# rw-linear-17mm-mk-1_0.net
KiCad netlist of a schematic drawn in EAGLE
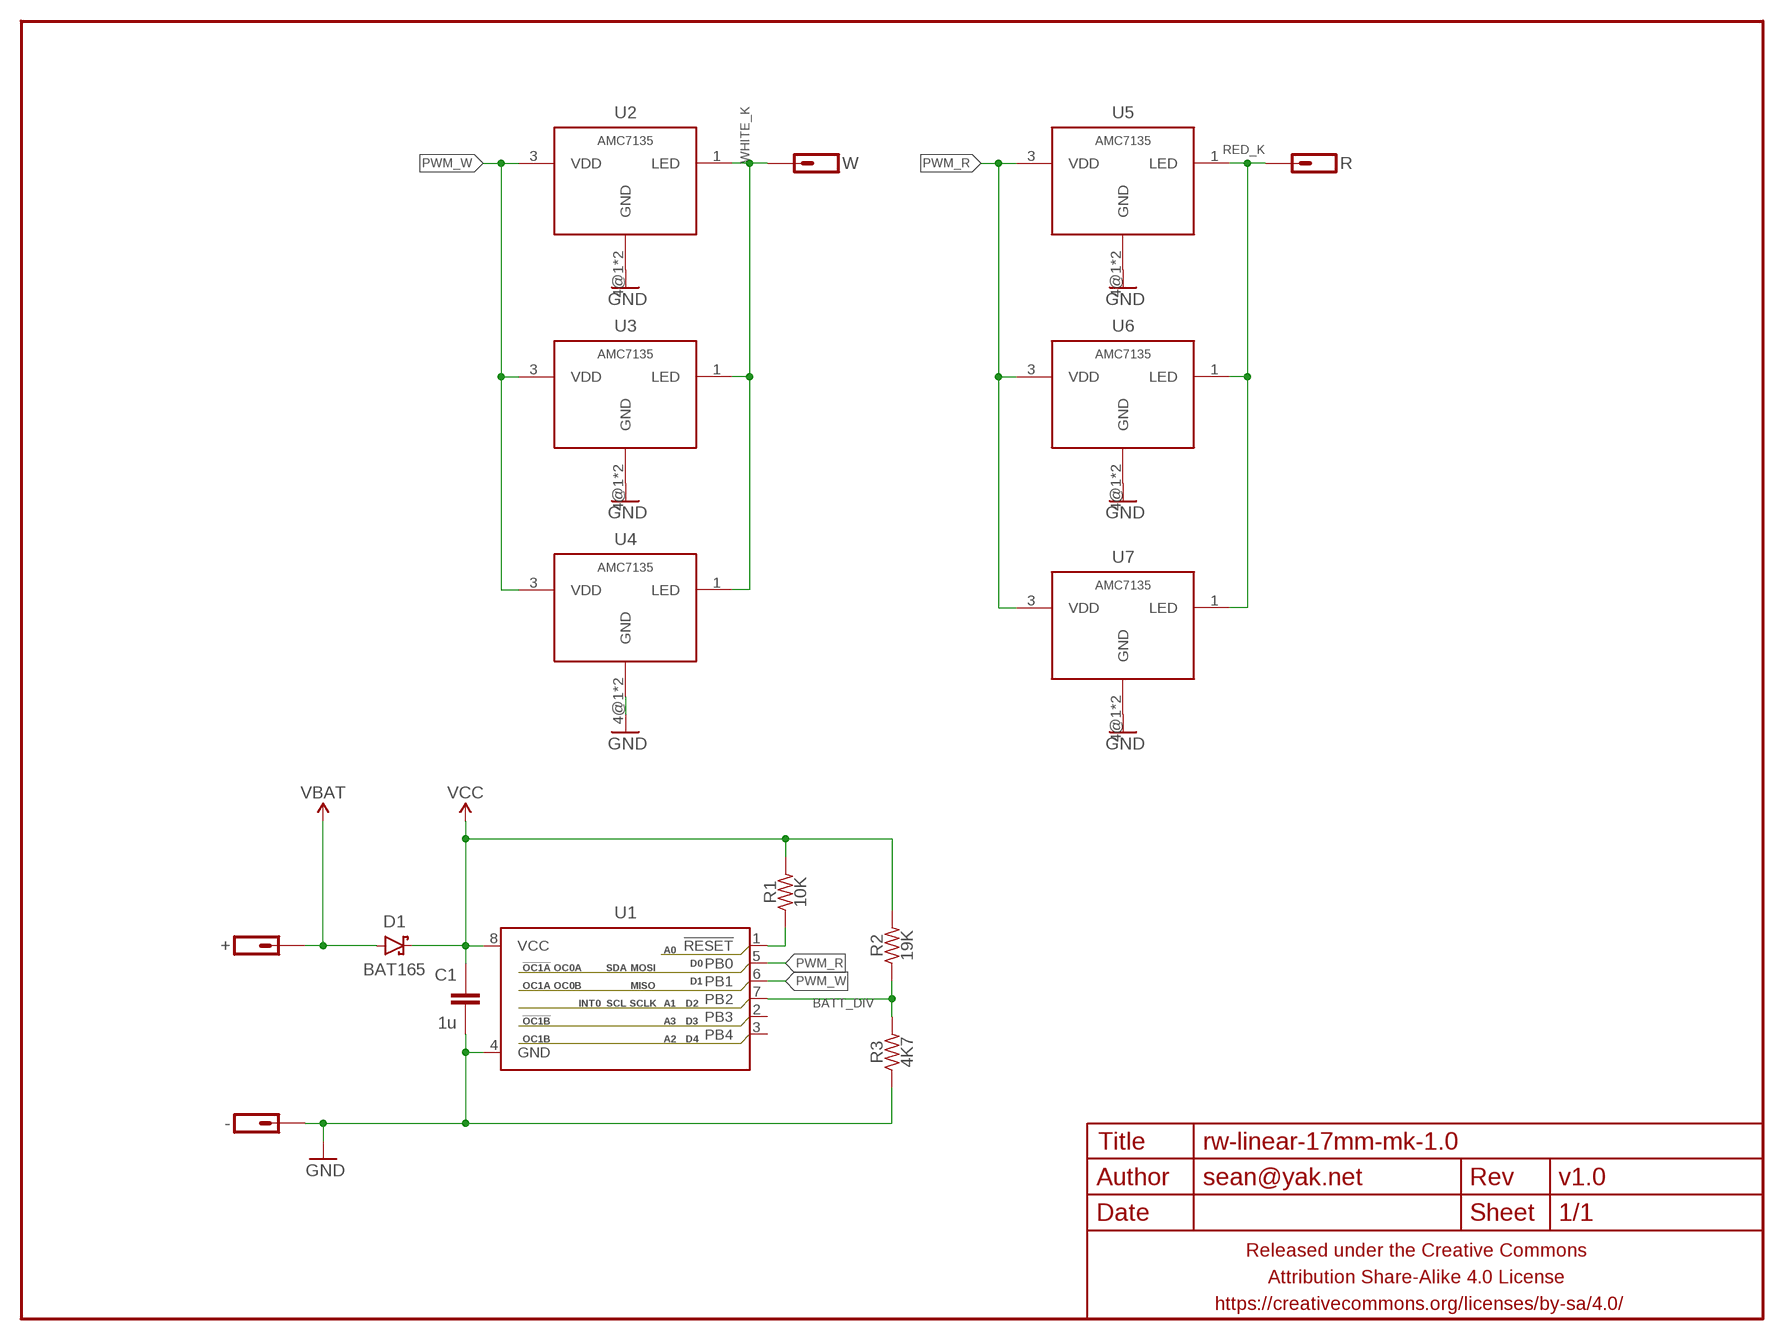
[diagram p0: schematic, sheet 1]

(export (version "E")
  (design (tool "Eeschema 10.0.6"))
  (components
    (comp (ref "+")
      (value "M01PTH-1.2MM-NS")
      (footprint "eagle-import:1X01-1.2MM-NS")
      (libsource (lib "eagle-import") (part "M01PTH-1.2MM-NS"))
    )
    (comp (ref "-")
      (value "M01NOT-A-VIA-NOPE")
      (footprint "eagle-import:1X01_NOSILK_NOSTOP")
      (libsource (lib "eagle-import") (part "M01NOT-A-VIA-NOPE"))
    )
    (comp (ref "C1")
      (value "1u")
      (footprint "eagle-import:C0402")
      (libsource (lib "eagle-import") (part "CAPACITOR-CERAMICC0402"))
    )
    (comp (ref "D1")
      (value "BAT165")
      (footprint "eagle-import:SOD323-SCHOTTKY")
      (libsource (lib "eagle-import") (part "DIODE-SCHOTTKYSOD323"))
    )
    (comp (ref "FRAME1")
      (value "FRAME-LETTERNO_PACKAGE")
      (footprint "eagle-import:DUMMY")
      (fields (field (name "DESIGNER") "sean@yak.net") (field (name "VERSION") "v1.0"))
      (libsource (lib "eagle-import") (part "FRAME-LETTERNO_PACKAGE"))
    )
    (comp (ref "R")
      (value "M01SMD-1.25MM-DIA")
      (footprint "eagle-import:1X01-SMD-1.25MM-DIA-NS")
      (libsource (lib "eagle-import") (part "M01SMD-1.25MM-DIA"))
    )
    (comp (ref "R1")
      (value "10K")
      (footprint "eagle-import:R0402")
      (libsource (lib "eagle-import") (part "RESISTORR0402"))
    )
    (comp (ref "R2")
      (value "19K")
      (footprint "eagle-import:R0402")
      (libsource (lib "eagle-import") (part "RESISTORR0402"))
    )
    (comp (ref "R3")
      (value "4K7")
      (footprint "eagle-import:R0402")
      (libsource (lib "eagle-import") (part "RESISTORR0402"))
    )
    (comp (ref "U1")
      (value "ATTINY13SOIC-NARROWPADS")
      (footprint "eagle-import:SO08-NARROWER")
      (libsource (lib "eagle-import") (part "ATTINY13SOIC-NARROWPADS"))
    )
    (comp (ref "U2")
      (value "AMC7135")
      (footprint "eagle-import:SOT89-NOTHERM")
      (libsource (lib "eagle-import") (part "AMC7135SOT-89-NOTHERM"))
    )
    (comp (ref "U3")
      (value "AMC7135")
      (footprint "eagle-import:SOT89-NOTHERM")
      (libsource (lib "eagle-import") (part "AMC7135SOT-89-NOTHERM"))
    )
    (comp (ref "U4")
      (value "AMC7135")
      (footprint "eagle-import:SOT89-NOTHERM")
      (libsource (lib "eagle-import") (part "AMC7135SOT-89-NOTHERM"))
    )
    (comp (ref "U5")
      (value "AMC7135")
      (footprint "eagle-import:SOT89-NOTHERM")
      (libsource (lib "eagle-import") (part "AMC7135SOT-89-NOTHERM"))
    )
    (comp (ref "U6")
      (value "AMC7135")
      (footprint "eagle-import:SOT89-NOTHERM")
      (libsource (lib "eagle-import") (part "AMC7135SOT-89-NOTHERM"))
    )
    (comp (ref "U7")
      (value "AMC7135")
      (footprint "eagle-import:SOT89-NOTHERM")
      (libsource (lib "eagle-import") (part "AMC7135SOT-89-NOTHERM"))
    )
    (comp (ref "W")
      (value "M01SMD-1.25MM-DIA")
      (footprint "eagle-import:1X01-SMD-1.25MM-DIA-NS")
      (libsource (lib "eagle-import") (part "M01SMD-1.25MM-DIA"))
    )
  )
  (nets
    (net (code "1") (name "/BATT_DIV") (class "Default")
      (node (ref "R2") (pin "1") (pinfunction "1_1") (pintype "passive"))
      (node (ref "R3") (pin "2") (pinfunction "2_2") (pintype "passive"))
      (node (ref "U1") (pin "7") (pinfunction "PB2_7") (pintype "bidirectional"))
    )
    (net (code "2") (name "/RED_K") (class "Default")
      (node (ref "R") (pin "P$1") (pinfunction "1_P$1") (pintype "passive"))
      (node (ref "U5") (pin "1") (pinfunction "LED_1") (pintype "bidirectional"))
      (node (ref "U6") (pin "1") (pinfunction "LED_1") (pintype "bidirectional"))
      (node (ref "U7") (pin "1") (pinfunction "LED_1") (pintype "bidirectional"))
    )
    (net (code "3") (name "/WHITE_K") (class "Default")
      (node (ref "U2") (pin "1") (pinfunction "LED_1") (pintype "bidirectional"))
      (node (ref "U3") (pin "1") (pinfunction "LED_1") (pintype "bidirectional"))
      (node (ref "U4") (pin "1") (pinfunction "LED_1") (pintype "bidirectional"))
      (node (ref "W") (pin "P$1") (pinfunction "1_P$1") (pintype "passive"))
    )
    (net (code "4") (name "GND") (class "Default")
      (node (ref "-") (pin "P$1") (pinfunction "1_P$1") (pintype "passive"))
      (node (ref "C1") (pin "2") (pinfunction "2_2") (pintype "passive"))
      (node (ref "R3") (pin "1") (pinfunction "1_1") (pintype "passive"))
      (node (ref "U1") (pin "4") (pinfunction "GND_4") (pintype "bidirectional"))
      (node (ref "U2") (pin "4@1") (pinfunction "GND_4@1") (pintype "bidirectional"))
      (node (ref "U2") (pin "4@2") (pinfunction "GND_4@2") (pintype "bidirectional"))
      (node (ref "U3") (pin "4@1") (pinfunction "GND_4@1") (pintype "bidirectional"))
      (node (ref "U3") (pin "4@2") (pinfunction "GND_4@2") (pintype "bidirectional"))
      (node (ref "U4") (pin "4@1") (pinfunction "GND_4@1") (pintype "bidirectional"))
      (node (ref "U4") (pin "4@2") (pinfunction "GND_4@2") (pintype "bidirectional"))
      (node (ref "U5") (pin "4@1") (pinfunction "GND_4@1") (pintype "bidirectional"))
      (node (ref "U5") (pin "4@2") (pinfunction "GND_4@2") (pintype "bidirectional"))
      (node (ref "U6") (pin "4@1") (pinfunction "GND_4@1") (pintype "bidirectional"))
      (node (ref "U6") (pin "4@2") (pinfunction "GND_4@2") (pintype "bidirectional"))
      (node (ref "U7") (pin "4@1") (pinfunction "GND_4@1") (pintype "bidirectional"))
      (node (ref "U7") (pin "4@2") (pinfunction "GND_4@2") (pintype "bidirectional"))
    )
    (net (code "5") (name "Net-(U1-~{RESET})") (class "Default")
      (node (ref "R1") (pin "1") (pinfunction "1_1") (pintype "passive"))
      (node (ref "U1") (pin "1") (pinfunction "~{RESET}_1") (pintype "bidirectional"))
    )
    (net (code "6") (name "PWM_R") (class "Default")
      (node (ref "U1") (pin "5") (pinfunction "PB0_5") (pintype "bidirectional"))
      (node (ref "U5") (pin "3") (pinfunction "VDD_3") (pintype "bidirectional"))
      (node (ref "U6") (pin "3") (pinfunction "VDD_3") (pintype "bidirectional"))
      (node (ref "U7") (pin "3") (pinfunction "VDD_3") (pintype "bidirectional"))
    )
    (net (code "7") (name "PWM_W") (class "Default")
      (node (ref "U1") (pin "6") (pinfunction "PB1_6") (pintype "bidirectional"))
      (node (ref "U2") (pin "3") (pinfunction "VDD_3") (pintype "bidirectional"))
      (node (ref "U3") (pin "3") (pinfunction "VDD_3") (pintype "bidirectional"))
      (node (ref "U4") (pin "3") (pinfunction "VDD_3") (pintype "bidirectional"))
    )
    (net (code "8") (name "VBAT") (class "Default")
      (node (ref "+") (pin "P$1") (pinfunction "1_P$1") (pintype "passive"))
      (node (ref "D1") (pin "A") (pinfunction "A_A") (pintype "passive"))
    )
    (net (code "9") (name "VCC") (class "Default")
      (node (ref "C1") (pin "1") (pinfunction "1_1") (pintype "passive"))
      (node (ref "D1") (pin "C") (pinfunction "C_C") (pintype "passive"))
      (node (ref "R1") (pin "2") (pinfunction "2_2") (pintype "passive"))
      (node (ref "R2") (pin "2") (pinfunction "2_2") (pintype "passive"))
      (node (ref "U1") (pin "8") (pinfunction "VCC_8") (pintype "bidirectional"))
    )
    (net (code "10") (name "unconnected-(U1-PB3-Pad2)") (class "Default")
      (node (ref "U1") (pin "2") (pinfunction "PB3_2") (pintype "bidirectional"))
    )
    (net (code "11") (name "unconnected-(U1-PB4-Pad3)") (class "Default")
      (node (ref "U1") (pin "3") (pinfunction "PB4_3") (pintype "bidirectional"))
    )
  )
)
